# Ece_473_Lab_4_Pre-Amp.net
KiCad netlist of a schematic drawn in EAGLE
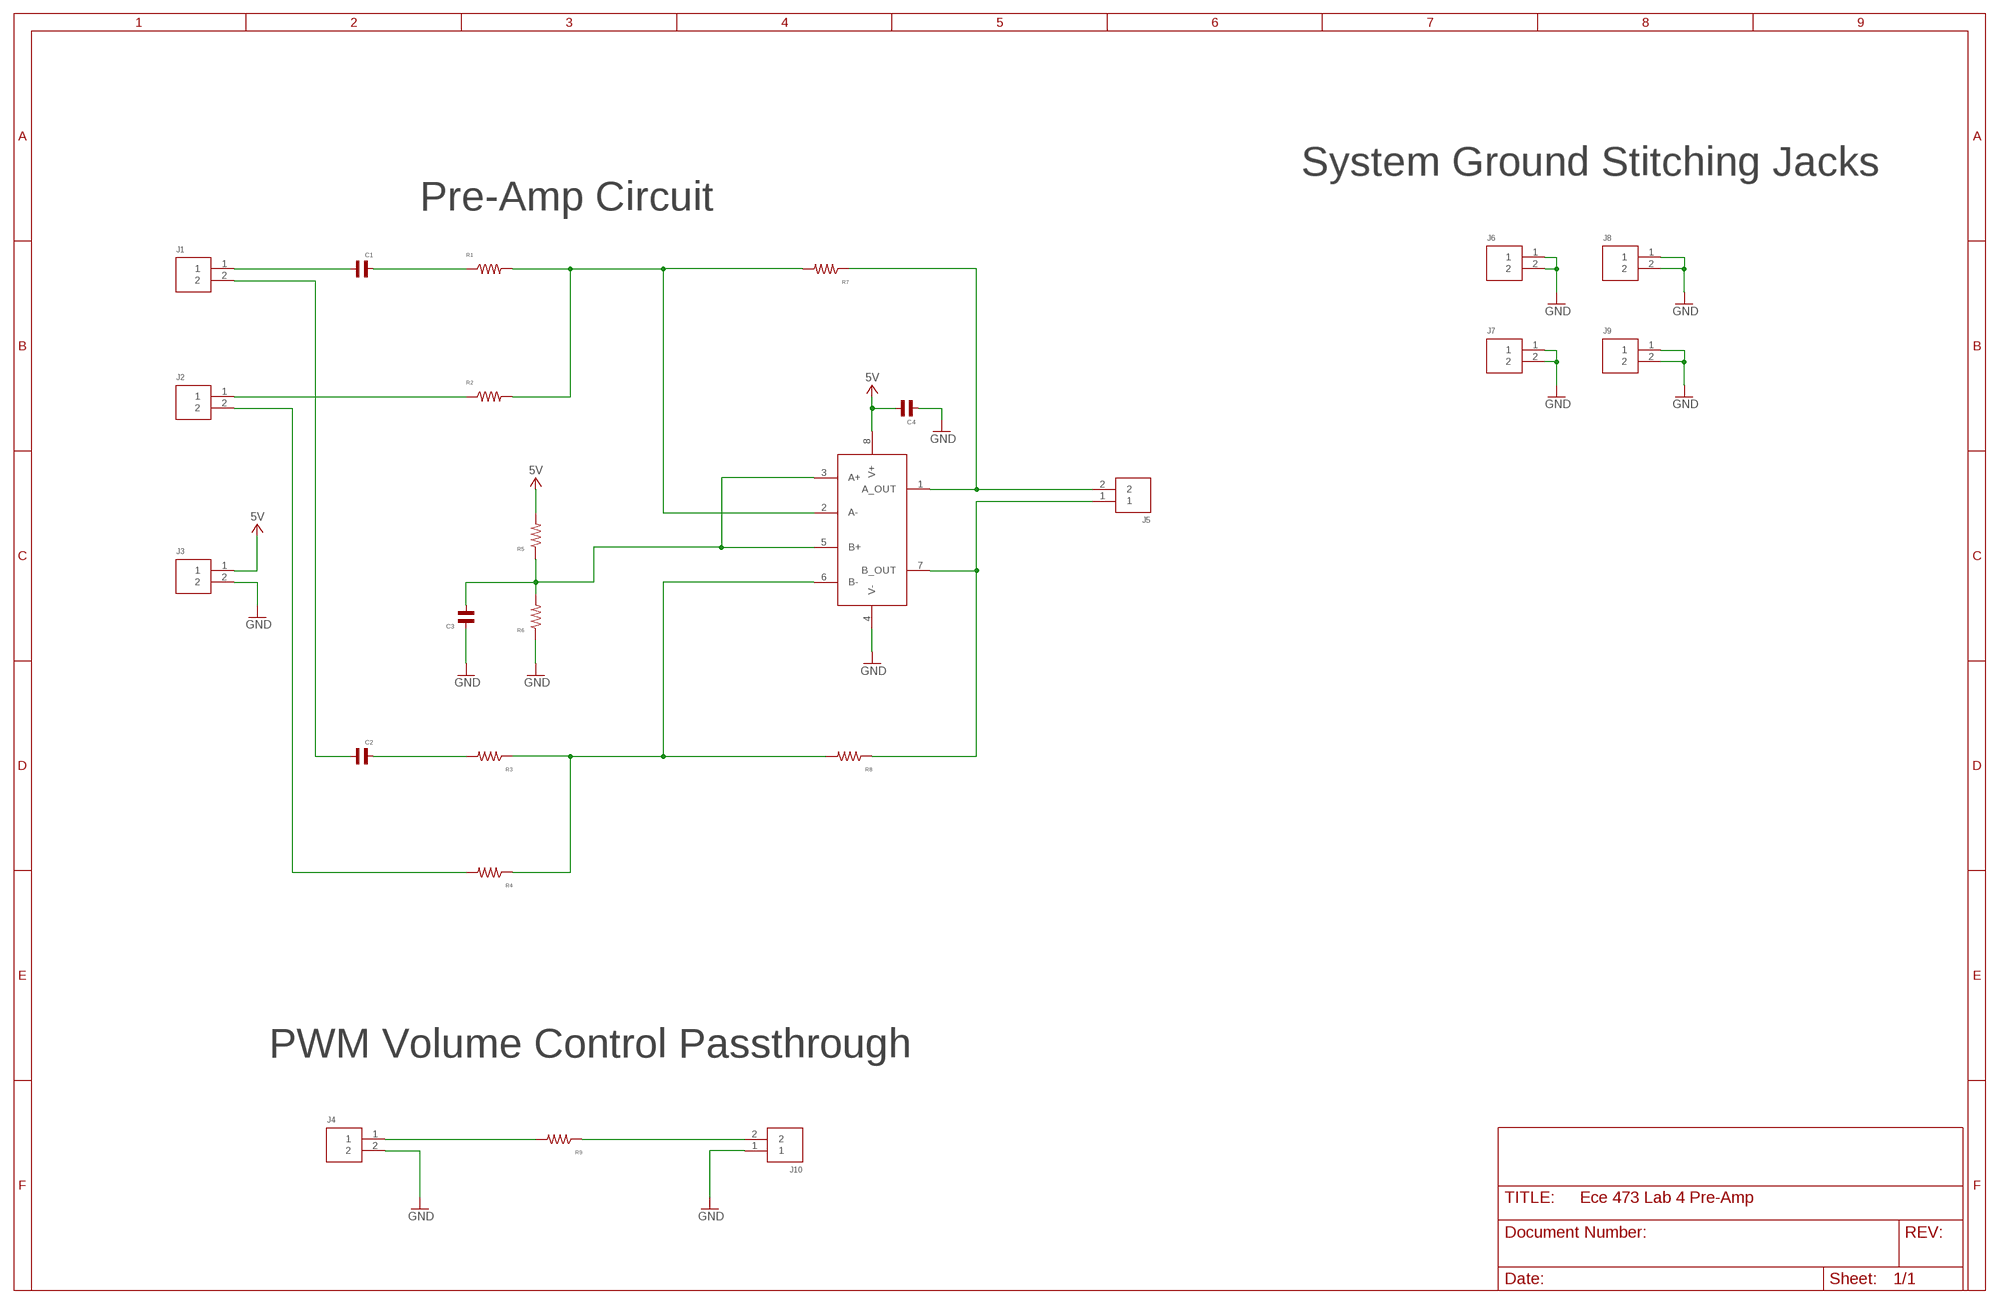
[diagram p0: schematic, sheet 1]

(export (version "E")
  (design (tool "Eeschema 10.0.6"))
  (components
    (comp (ref "C1")
      (value "0.1uF")
      (footprint "eagle-import:CAP_THROUGH-HOLE")
      (fields (field (name "MPN") "K104M15X7RF53L2"))
      (libsource (lib "eagle-import") (part "CAPACITOR_THROUGH-HOLE_0.1UF"))
    )
    (comp (ref "C2")
      (value "0.1uF")
      (footprint "eagle-import:CAP_THROUGH-HOLE")
      (fields (field (name "MPN") "K104M15X7RF53L2"))
      (libsource (lib "eagle-import") (part "CAPACITOR_THROUGH-HOLE_0.1UF"))
    )
    (comp (ref "C3")
      (value "0.1uF")
      (footprint "eagle-import:CAP_THROUGH-HOLE")
      (fields (field (name "MPN") "K104M15X7RF53L2"))
      (libsource (lib "eagle-import") (part "CAPACITOR_THROUGH-HOLE_0.1UF"))
    )
    (comp (ref "C4")
      (value "0.1uF")
      (footprint "eagle-import:CAP_THROUGH-HOLE")
      (fields (field (name "MPN") "K104M15X7RF53L2"))
      (libsource (lib "eagle-import") (part "CAPACITOR_THROUGH-HOLE_0.1UF"))
    )
    (comp (ref "J1")
      (value "2x1")
      (footprint "eagle-import:HDRV2W64P254_1X2_467X234X838B")
      (libsource (lib "eagle-import") (part "CONNECTOR-2_2X1"))
    )
    (comp (ref "J2")
      (value "2x1")
      (footprint "eagle-import:HDRV2W64P254_1X2_467X234X838B")
      (libsource (lib "eagle-import") (part "CONNECTOR-2_2X1"))
    )
    (comp (ref "J3")
      (value "2x1")
      (footprint "eagle-import:HDRV2W64P254_1X2_467X234X838B")
      (libsource (lib "eagle-import") (part "CONNECTOR-2_2X1"))
    )
    (comp (ref "J4")
      (value "2x1")
      (footprint "eagle-import:HDRV2W64P254_1X2_467X234X838B")
      (libsource (lib "eagle-import") (part "CONNECTOR-2_2X1"))
    )
    (comp (ref "J5")
      (value "2x1")
      (footprint "eagle-import:HDRV2W64P254_1X2_467X234X838B")
      (libsource (lib "eagle-import") (part "CONNECTOR-2_2X1"))
    )
    (comp (ref "J6")
      (value "2x1")
      (footprint "eagle-import:HDRV2W64P254_1X2_467X234X838B")
      (libsource (lib "eagle-import") (part "CONNECTOR-2_2X1"))
    )
    (comp (ref "J7")
      (value "2x1")
      (footprint "eagle-import:HDRV2W64P254_1X2_467X234X838B")
      (libsource (lib "eagle-import") (part "CONNECTOR-2_2X1"))
    )
    (comp (ref "J8")
      (value "2x1")
      (footprint "eagle-import:HDRV2W64P254_1X2_467X234X838B")
      (libsource (lib "eagle-import") (part "CONNECTOR-2_2X1"))
    )
    (comp (ref "J9")
      (value "2x1")
      (footprint "eagle-import:HDRV2W64P254_1X2_467X234X838B")
      (libsource (lib "eagle-import") (part "CONNECTOR-2_2X1"))
    )
    (comp (ref "J10")
      (value "2x1")
      (footprint "eagle-import:HDRV2W64P254_1X2_467X234X838B")
      (libsource (lib "eagle-import") (part "CONNECTOR-2_2X1"))
    )
    (comp (ref "R1")
      (value "200k")
      (footprint "eagle-import:RESISTOR_THROUGH-HOLE")
      (libsource (lib "eagle-import") (part "RESISTOR_THROUGH-HOLE_200K"))
    )
    (comp (ref "R2")
      (value "3k")
      (footprint "eagle-import:RESISTOR_THROUGH-HOLE")
      (libsource (lib "eagle-import") (part "RESISTOR_THROUGH-HOLE_3K"))
    )
    (comp (ref "R3")
      (value "RESISTOR_THROUGH-HOLE")
      (footprint "eagle-import:RESISTOR_THROUGH-HOLE")
      (libsource (lib "eagle-import") (part "RESISTOR_THROUGH-HOLE"))
    )
    (comp (ref "R4")
      (value "3k")
      (footprint "eagle-import:RESISTOR_THROUGH-HOLE")
      (libsource (lib "eagle-import") (part "RESISTOR_THROUGH-HOLE_3K"))
    )
    (comp (ref "R5")
      (value "100k")
      (footprint "eagle-import:RESISTOR_THROUGH-HOLE")
      (libsource (lib "eagle-import") (part "RESISTOR_THROUGH-HOLE_100K"))
    )
    (comp (ref "R6")
      (value "100k")
      (footprint "eagle-import:RESISTOR_THROUGH-HOLE")
      (libsource (lib "eagle-import") (part "RESISTOR_THROUGH-HOLE_100K"))
    )
    (comp (ref "R7")
      (value "10k")
      (footprint "eagle-import:RESISTOR_THROUGH-HOLE")
      (libsource (lib "eagle-import") (part "RESISTOR_THROUGH-HOLE_10K"))
    )
    (comp (ref "R8")
      (value "10k")
      (footprint "eagle-import:RESISTOR_THROUGH-HOLE")
      (libsource (lib "eagle-import") (part "RESISTOR_THROUGH-HOLE_10K"))
    )
    (comp (ref "R9")
      (value "100k")
      (footprint "eagle-import:RESISTOR_THROUGH-HOLE")
      (libsource (lib "eagle-import") (part "RESISTOR_THROUGH-HOLE_100K"))
    )
    (comp (ref "U1")
      (value "LMC6032")
      (footprint "eagle-import:PDIP-8PIN")
      (fields (field (name "MPN") "LMC6032IN/NOPB"))
      (libsource (lib "eagle-import") (part "OP-AMP_PDIP-8PINLMC6032"))
    )
  )
  (nets
    (net (code "1") (name "5V") (class "Default")
      (node (ref "C4") (pin "2") (pinfunction "P$2_2") (pintype "passive"))
      (node (ref "J3") (pin "1") (pinfunction "1_1") (pintype "bidirectional"))
      (node (ref "R5") (pin "2") (pinfunction "P$2_2") (pintype "passive"))
      (node (ref "U1") (pin "8") (pinfunction "V+_8") (pintype "passive"))
    )
    (net (code "2") (name "GND") (class "Default")
      (node (ref "C3") (pin "1") (pinfunction "P$1_1") (pintype "passive"))
      (node (ref "C4") (pin "1") (pinfunction "P$1_1") (pintype "passive"))
      (node (ref "J10") (pin "1") (pinfunction "1_1") (pintype "bidirectional"))
      (node (ref "J3") (pin "2") (pinfunction "2_2") (pintype "bidirectional"))
      (node (ref "J4") (pin "2") (pinfunction "2_2") (pintype "bidirectional"))
      (node (ref "J6") (pin "1") (pinfunction "1_1") (pintype "bidirectional"))
      (node (ref "J6") (pin "2") (pinfunction "2_2") (pintype "bidirectional"))
      (node (ref "J7") (pin "1") (pinfunction "1_1") (pintype "bidirectional"))
      (node (ref "J7") (pin "2") (pinfunction "2_2") (pintype "bidirectional"))
      (node (ref "J8") (pin "1") (pinfunction "1_1") (pintype "bidirectional"))
      (node (ref "J8") (pin "2") (pinfunction "2_2") (pintype "bidirectional"))
      (node (ref "J9") (pin "1") (pinfunction "1_1") (pintype "bidirectional"))
      (node (ref "J9") (pin "2") (pinfunction "2_2") (pintype "bidirectional"))
      (node (ref "R6") (pin "1") (pinfunction "P$1_1") (pintype "passive"))
      (node (ref "U1") (pin "4") (pinfunction "V-_4") (pintype "passive"))
    )
    (net (code "3") (name "Net-(C1-P$1)") (class "Default")
      (node (ref "C1") (pin "1") (pinfunction "P$1_1") (pintype "passive"))
      (node (ref "J1") (pin "1") (pinfunction "1_1") (pintype "bidirectional"))
    )
    (net (code "4") (name "Net-(C1-P$2)") (class "Default")
      (node (ref "C1") (pin "2") (pinfunction "P$2_2") (pintype "passive"))
      (node (ref "R1") (pin "1") (pinfunction "P$1_1") (pintype "passive"))
    )
    (net (code "5") (name "Net-(C2-P$1)") (class "Default")
      (node (ref "C2") (pin "1") (pinfunction "P$1_1") (pintype "passive"))
      (node (ref "J1") (pin "2") (pinfunction "2_2") (pintype "bidirectional"))
    )
    (net (code "6") (name "Net-(C2-P$2)") (class "Default")
      (node (ref "C2") (pin "2") (pinfunction "P$2_2") (pintype "passive"))
      (node (ref "R3") (pin "2") (pinfunction "P$2_2") (pintype "passive"))
    )
    (net (code "7") (name "Net-(C3-P$2)") (class "Default")
      (node (ref "C3") (pin "2") (pinfunction "P$2_2") (pintype "passive"))
      (node (ref "R5") (pin "1") (pinfunction "P$1_1") (pintype "passive"))
      (node (ref "R6") (pin "2") (pinfunction "P$2_2") (pintype "passive"))
      (node (ref "U1") (pin "3") (pinfunction "A+_3") (pintype "passive"))
      (node (ref "U1") (pin "5") (pinfunction "B+_5") (pintype "passive"))
    )
    (net (code "8") (name "Net-(R1-P$2)") (class "Default")
      (node (ref "R1") (pin "2") (pinfunction "P$2_2") (pintype "passive"))
      (node (ref "R2") (pin "2") (pinfunction "P$2_2") (pintype "passive"))
      (node (ref "R7") (pin "2") (pinfunction "P$2_2") (pintype "passive"))
      (node (ref "U1") (pin "2") (pinfunction "A-_2") (pintype "passive"))
    )
    (net (code "9") (name "Net-(R2-P$1)") (class "Default")
      (node (ref "J2") (pin "1") (pinfunction "1_1") (pintype "bidirectional"))
      (node (ref "R2") (pin "1") (pinfunction "P$1_1") (pintype "passive"))
    )
    (net (code "10") (name "Net-(R3-P$1)") (class "Default")
      (node (ref "R3") (pin "1") (pinfunction "P$1_1") (pintype "passive"))
      (node (ref "R4") (pin "1") (pinfunction "P$1_1") (pintype "passive"))
      (node (ref "R8") (pin "2") (pinfunction "P$2_2") (pintype "passive"))
      (node (ref "U1") (pin "6") (pinfunction "B-_6") (pintype "passive"))
    )
    (net (code "11") (name "Net-(R4-P$2)") (class "Default")
      (node (ref "J2") (pin "2") (pinfunction "2_2") (pintype "bidirectional"))
      (node (ref "R4") (pin "2") (pinfunction "P$2_2") (pintype "passive"))
    )
    (net (code "12") (name "Net-(R7-P$1)") (class "Default")
      (node (ref "J5") (pin "2") (pinfunction "2_2") (pintype "bidirectional"))
      (node (ref "R7") (pin "1") (pinfunction "P$1_1") (pintype "passive"))
      (node (ref "U1") (pin "1") (pinfunction "A_OUT_1") (pintype "passive"))
    )
    (net (code "13") (name "Net-(R8-P$1)") (class "Default")
      (node (ref "J5") (pin "1") (pinfunction "1_1") (pintype "bidirectional"))
      (node (ref "R8") (pin "1") (pinfunction "P$1_1") (pintype "passive"))
      (node (ref "U1") (pin "7") (pinfunction "B_OUT_7") (pintype "passive"))
    )
    (net (code "14") (name "Net-(R9-P$1)") (class "Default")
      (node (ref "J10") (pin "2") (pinfunction "2_2") (pintype "bidirectional"))
      (node (ref "R9") (pin "1") (pinfunction "P$1_1") (pintype "passive"))
    )
    (net (code "15") (name "Net-(R9-P$2)") (class "Default")
      (node (ref "J4") (pin "1") (pinfunction "1_1") (pintype "bidirectional"))
      (node (ref "R9") (pin "2") (pinfunction "P$2_2") (pintype "passive"))
    )
  )
)
